# D2_2020-10-05_16-15-53.net
KiCad netlist of a schematic drawn in EasyEDA
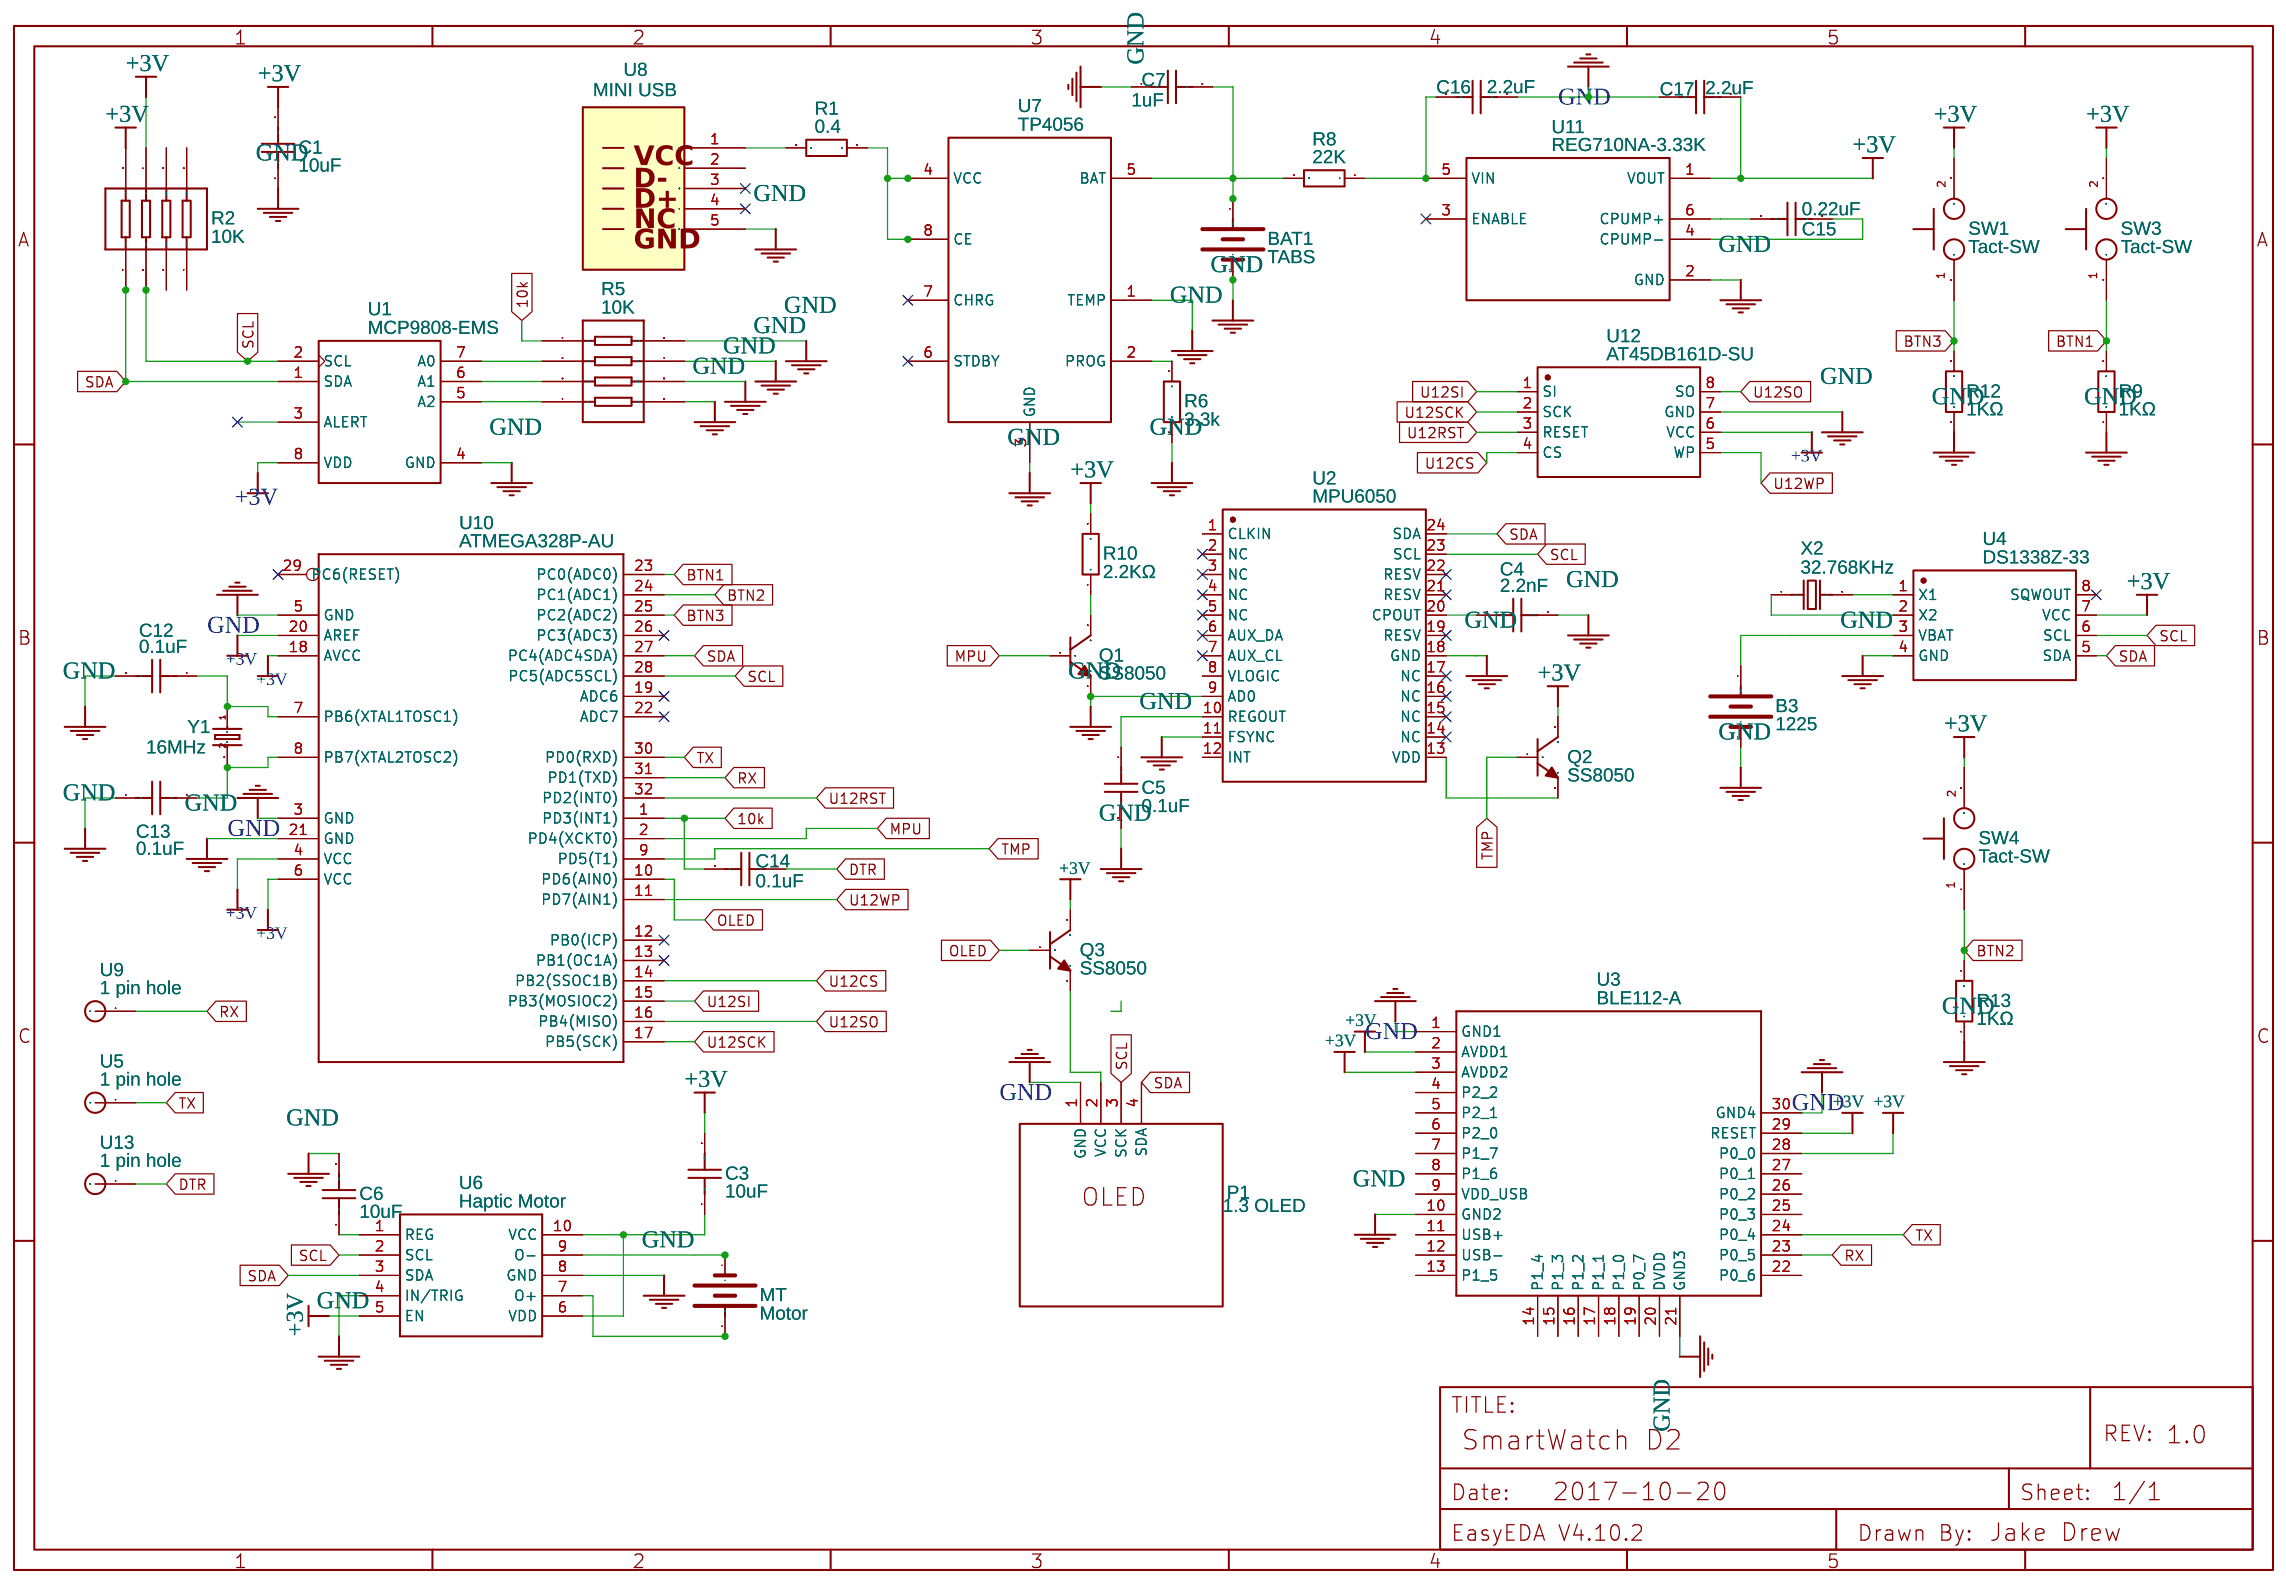
[diagram p0: schematic sheet]

(export (version "E")
  (design (tool "Eeschema 10.0.6"))
  (components
    (comp (ref "B3")
      (value "1225")
      (fields (field (name "BOM_Manufacturer Part") "?"))
      (libsource (lib "") (part "Unknown_850_335"))
    )
    (comp (ref "BAT1")
      (value "TABS")
      (fields (field (name "BOM_Manufacturer Part") "?"))
      (libsource (lib "") (part "Unknown_600_105"))
    )
    (comp (ref "C1")
      (value "10uF")
      (fields
        (field (name "BOM_Manufacturer Part") "0805B105K250NT")
        (field (name "BOM_Supplier Part") "C89190")
      )
      (libsource (lib "") (part "Unknown_130_60"))
    )
    (comp (ref "C3")
      (value "10uF")
      (fields
        (field (name "BOM_Manufacturer Part") "0805B105K250NT")
        (field (name "BOM_Supplier Part") "C89190")
      )
      (libsource (lib "") (part "Unknown_340_565"))
    )
    (comp (ref "C4")
      (value "2.2nF")
      (fields
        (field (name "BOM_Manufacturer Part") "0805B105K250NT")
        (field (name "BOM_Supplier Part") "C89190")
      )
      (libsource (lib "") (part "Unknown_740_290"))
    )
    (comp (ref "C5")
      (value "0.1uF")
      (fields
        (field (name "BOM_Manufacturer Part") "0805B105K250NT")
        (field (name "BOM_Supplier Part") "C89190")
      )
      (libsource (lib "") (part "Unknown_545_375"))
    )
    (comp (ref "C6")
      (value "10uF")
      (fields
        (field (name "BOM_Manufacturer Part") "0805B105K250NT")
        (field (name "BOM_Supplier Part") "C89190")
      )
      (libsource (lib "") (part "Unknown_160_575"))
    )
    (comp (ref "C7")
      (value "1uF")
      (fields
        (field (name "BOM_Manufacturer Part") "0805B105K250NT")
        (field (name "BOM_Supplier Part") "C89190")
      )
      (libsource (lib "") (part "Unknown_570_30"))
    )
    (comp (ref "C12")
      (value "0.1uF")
      (fields
        (field (name "BOM_Manufacturer Part") "0805B105K250NT")
        (field (name "BOM_Supplier Part") "C89190")
      )
      (libsource (lib "") (part "Unknown_70_320"))
    )
    (comp (ref "C13")
      (value "0.1uF")
      (fields
        (field (name "BOM_Manufacturer Part") "0805B105K250NT")
        (field (name "BOM_Supplier Part") "C89190")
      )
      (libsource (lib "") (part "Unknown_70_380"))
    )
    (comp (ref "C14")
      (value "0.1uF")
      (fields
        (field (name "BOM_Manufacturer Part") "0805B105K250NT")
        (field (name "BOM_Supplier Part") "C89190")
      )
      (libsource (lib "") (part "Unknown_360_415"))
    )
    (comp (ref "C15")
      (value "0.22uF")
      (fields
        (field (name "BOM_Manufacturer Part") "0805B105K250NT")
        (field (name "BOM_Supplier Part") "C89190")
      )
      (libsource (lib "") (part "Unknown_875_95"))
    )
    (comp (ref "C16")
      (value "2.2uF")
      (fields
        (field (name "BOM_Manufacturer Part") "0805B105K250NT")
        (field (name "BOM_Supplier Part") "C89190")
      )
      (libsource (lib "") (part "Unknown_720_35"))
    )
    (comp (ref "C17")
      (value "2.2uF")
      (fields
        (field (name "BOM_Manufacturer Part") "0805B105K250NT")
        (field (name "BOM_Supplier Part") "C89190")
      )
      (libsource (lib "") (part "Unknown_830_35"))
    )
    (comp (ref "MT")
      (value "Motor")
      (fields (field (name "BOM_Manufacturer Part") "?"))
      (libsource (lib "") (part "Unknown_350_625"))
    )
    (comp (ref "P1")
      (value "1.3 OLED")
      (fields (field (name "BOM_Manufacturer Part") "?"))
      (libsource (lib "") (part "Unknown_575_630"))
    )
    (comp (ref "Q1")
      (value "SS8050")
      (fields (field (name "BOM_Supplier Part") "C2150"))
      (libsource (lib "") (part "Unknown_520_310"))
    )
    (comp (ref "Q2")
      (value "SS8050")
      (fields (field (name "BOM_Supplier Part") "C2150"))
      (libsource (lib "") (part "Unknown_750_360"))
    )
    (comp (ref "Q3")
      (value "SS8050")
      (fields (field (name "BOM_Supplier Part") "C2150"))
      (libsource (lib "") (part "Unknown_510_455"))
    )
    (comp (ref "R1")
      (value "0.4")
      (fields
        (field (name "BOM_Manufacturer Part") "0805W8F147KT5E")
        (field (name "BOM_Supplier Part") "C68930")
      )
      (libsource (lib "") (part "Unknown_400_60"))
    )
    (comp (ref "R2")
      (value "10K")
      (fields
        (field (name "BOM_Manufacturer Part") "4D03WGJ0102T5E")
        (field (name "BOM_Supplier Part") "C20197")
      )
      (libsource (lib "") (part "Unknown_70_95"))
    )
    (comp (ref "R5")
      (value "10K")
      (fields
        (field (name "BOM_Manufacturer Part") "4D03WGJ0102T5E")
        (field (name "BOM_Supplier Part") "C20197")
      )
      (libsource (lib "") (part "Unknown_295_170"))
    )
    (comp (ref "R6")
      (value "3.3k")
      (fields
        (field (name "BOM_Manufacturer Part") "1210W3F680KT5E")
        (field (name "BOM_Supplier Part") "C38887")
      )
      (libsource (lib "") (part "Unknown_570_185"))
    )
    (comp (ref "R8")
      (value "22K")
      (fields
        (field (name "BOM_Manufacturer Part") "1206W4F1001T5E")
        (field (name "BOM_Supplier Part") "C4410")
      )
      (libsource (lib "") (part "Unknown_645_75"))
    )
    (comp (ref "R9")
      (value "1KΩ")
      (fields
        (field (name "BOM_Manufacturer Part") "1206W4F1001T5E")
        (field (name "BOM_Supplier Part") "C4410")
      )
      (libsource (lib "") (part "Unknown_1030_180"))
    )
    (comp (ref "R10")
      (value "2.2KΩ")
      (fields
        (field (name "BOM_Manufacturer Part") "0805W8F2201T5E")
        (field (name "BOM_Supplier Part") "C17520")
      )
      (libsource (lib "") (part "Unknown_530_260"))
    )
    (comp (ref "R12")
      (value "1KΩ")
      (fields
        (field (name "BOM_Manufacturer Part") "1206W4F1001T5E")
        (field (name "BOM_Supplier Part") "C4410")
      )
      (libsource (lib "") (part "Unknown_955_180"))
    )
    (comp (ref "R13")
      (value "1KΩ")
      (fields
        (field (name "BOM_Manufacturer Part") "1206W4F1001T5E")
        (field (name "BOM_Supplier Part") "C4410")
      )
      (libsource (lib "") (part "Unknown_960_480"))
    )
    (comp (ref "SW1")
      (value "Tact-SW")
      (fields (field (name "BOM_Manufacturer Part") "TL3330AF260QG"))
      (libsource (lib "") (part "Unknown_955_100"))
    )
    (comp (ref "SW3")
      (value "Tact-SW")
      (fields (field (name "BOM_Manufacturer Part") "TL3330AF260QG"))
      (libsource (lib "") (part "Unknown_1030_100"))
    )
    (comp (ref "SW4")
      (value "Tact-SW")
      (fields (field (name "BOM_Manufacturer Part") "TL3330AF260QG"))
      (libsource (lib "") (part "Unknown_960_400"))
    )
    (comp (ref "U1")
      (value "MCP9808-EMS")
      (fields (field (name "BOM_Manufacturer Part") "?"))
      (libsource (lib "") (part "Unknown_180_195"))
    )
    (comp (ref "U2")
      (value "MPU6050")
      (fields (field (name "BOM_Supplier Part") "C24112"))
      (libsource (lib "") (part "Unknown_645_240"))
    )
    (comp (ref "U3")
      (value "BLE112-A")
      (fields (field (name "BOM_Manufacturer Part") "?"))
      (libsource (lib "") (part "Unknown_690_505"))
    )
    (comp (ref "U4")
      (value "DS1338Z-33")
      (fields (field (name "BOM_Supplier Part") "C49105"))
      (libsource (lib "") (part "Unknown_975_270"))
    )
    (comp (ref "U5") (value "1 pin hole") (libsource (lib "") (part "Unknown_40_530")))
    (comp (ref "U6")
      (value "Haptic Motor")
      (fields (field (name "BOM_Manufacturer Part") "?"))
      (libsource (lib "") (part "Unknown_230_615"))
    )
    (comp (ref "U7")
      (value "TP4056")
      (fields (field (name "BOM_Supplier Part") "C16581"))
      (libsource (lib "") (part "Unknown_500_135"))
    )
    (comp (ref "U8")
      (value "MINI USB")
      (fields (field (name "BOM_Manufacturer Part") "?"))
      (libsource (lib "") (part "Unknown_330_80"))
    )
    (comp (ref "U9") (value "1 pin hole") (libsource (lib "") (part "Unknown_40_485")))
    (comp (ref "U10") (value "ATMEGA328P-AU") (libsource (lib "") (part "Unknown_225_385")))
    (comp (ref "U11")
      (value "REG710NA-3.33K")
      (fields (field (name "BOM_Manufacturer Part") "?"))
      (libsource (lib "") (part "Unknown_765_105"))
    )
    (comp (ref "U12")
      (value "AT45DB161D-SU")
      (fields (field (name "BOM_Manufacturer Part") "?"))
      (libsource (lib "") (part "Unknown_790_170"))
    )
    (comp (ref "U13") (value "1 pin hole") (libsource (lib "") (part "Unknown_40_570")))
    (comp (ref "X2")
      (value "32.768KHz")
      (fields
        (field (name "BOM_Manufacturer Part") "DT-38 32.768KHz")
        (field (name "BOM_Supplier Part") "C93228")
      )
      (libsource (lib "") (part "Unknown_885_280"))
    )
    (comp (ref "Y1")
      (value "16MHz")
      (fields (field (name "BOM_Manufacturer Part") "X053201602002"))
      (libsource (lib "") (part "Unknown_105_350"))
    )
  )
  (nets
    (net (code "1") (name "+3V") (class "Default")
      (node (ref "C1") (pin "2") (pinfunction "2_2") (pintype "unspecified"))
      (node (ref "C17") (pin "2") (pinfunction "2_2") (pintype "unspecified"))
      (node (ref "C3") (pin "2") (pinfunction "2_2") (pintype "unspecified"))
      (node (ref "Q2") (pin "3") (pinfunction "C_3") (pintype "unspecified"))
      (node (ref "Q3") (pin "3") (pinfunction "C_3") (pintype "unspecified"))
      (node (ref "R10") (pin "2") (pinfunction "2_2") (pintype "input"))
      (node (ref "R2") (pin "7") (pinfunction "7_7") (pintype "input"))
      (node (ref "R2") (pin "8") (pinfunction "8_8") (pintype "input"))
      (node (ref "SW1") (pin "2") (pinfunction "2_2") (pintype "unspecified"))
      (node (ref "SW3") (pin "2") (pinfunction "2_2") (pintype "unspecified"))
      (node (ref "SW4") (pin "2") (pinfunction "2_2") (pintype "unspecified"))
      (node (ref "U1") (pin "8") (pinfunction "VDD_8") (pintype "passive"))
      (node (ref "U10") (pin "18") (pinfunction "AVCC_18") (pintype "unspecified"))
      (node (ref "U10") (pin "20") (pinfunction "AREF_20") (pintype "unspecified"))
      (node (ref "U10") (pin "4") (pinfunction "VCC_4") (pintype "unspecified"))
      (node (ref "U10") (pin "6") (pinfunction "VCC_6") (pintype "unspecified"))
      (node (ref "U11") (pin "1") (pinfunction "VOUT_1") (pintype "passive"))
      (node (ref "U12") (pin "6") (pinfunction "VCC_6") (pintype "unspecified"))
      (node (ref "U3") (pin "2") (pinfunction "AVDD1_2") (pintype "unspecified"))
      (node (ref "U3") (pin "28") (pinfunction "P0_0_28") (pintype "unspecified"))
      (node (ref "U3") (pin "29") (pinfunction "RESET_29") (pintype "unspecified"))
      (node (ref "U3") (pin "3") (pinfunction "AVDD2_3") (pintype "unspecified"))
      (node (ref "U4") (pin "7") (pinfunction "VCC_7") (pintype "unspecified"))
      (node (ref "U6") (pin "5") (pinfunction "EN_5") (pintype "unspecified"))
    )
    (net (code "2") (name "10k") (class "Default")
      (node (ref "C14") (pin "2") (pinfunction "2_2") (pintype "unspecified"))
      (node (ref "R5") (pin "1") (pinfunction "1_1") (pintype "input"))
      (node (ref "U10") (pin "1") (pinfunction "PD3(INT1)_1") (pintype "unspecified"))
    )
    (net (code "3") (name "BTN1") (class "Default")
      (node (ref "R9") (pin "2") (pinfunction "2_2") (pintype "input"))
      (node (ref "SW3") (pin "1") (pinfunction "1_1") (pintype "unspecified"))
      (node (ref "U10") (pin "23") (pinfunction "PC0(ADC0)_23") (pintype "unspecified"))
    )
    (net (code "4") (name "BTN2") (class "Default")
      (node (ref "R13") (pin "2") (pinfunction "2_2") (pintype "input"))
      (node (ref "SW4") (pin "1") (pinfunction "1_1") (pintype "unspecified"))
      (node (ref "U10") (pin "24") (pinfunction "PC1(ADC1)_24") (pintype "unspecified"))
    )
    (net (code "5") (name "BTN3") (class "Default")
      (node (ref "R12") (pin "2") (pinfunction "2_2") (pintype "input"))
      (node (ref "SW1") (pin "1") (pinfunction "1_1") (pintype "unspecified"))
      (node (ref "U10") (pin "25") (pinfunction "PC2(ADC2)_25") (pintype "unspecified"))
    )
    (net (code "6") (name "DTR") (class "Default")
      (node (ref "C14") (pin "1") (pinfunction "1_1") (pintype "unspecified"))
      (node (ref "U13") (pin "1") (pinfunction "1_1") (pintype "unspecified"))
    )
    (net (code "7") (name "GND") (class "Default")
      (node (ref "B3") (pin "-") (pinfunction "-_-") (pintype "passive"))
      (node (ref "BAT1") (pin "-") (pinfunction "-_-") (pintype "passive"))
      (node (ref "C1") (pin "1") (pinfunction "1_1") (pintype "unspecified"))
      (node (ref "C12") (pin "2") (pinfunction "2_2") (pintype "unspecified"))
      (node (ref "C13") (pin "1") (pinfunction "1_1") (pintype "unspecified"))
      (node (ref "C16") (pin "1") (pinfunction "1_1") (pintype "unspecified"))
      (node (ref "C17") (pin "1") (pinfunction "1_1") (pintype "unspecified"))
      (node (ref "C4") (pin "1") (pinfunction "1_1") (pintype "unspecified"))
      (node (ref "C5") (pin "2") (pinfunction "2_2") (pintype "unspecified"))
      (node (ref "C6") (pin "2") (pinfunction "2_2") (pintype "unspecified"))
      (node (ref "C7") (pin "1") (pinfunction "1_1") (pintype "unspecified"))
      (node (ref "P1") (pin "1") (pinfunction "GND_1") (pintype "unspecified"))
      (node (ref "Q1") (pin "2") (pinfunction "E_2") (pintype "unspecified"))
      (node (ref "R12") (pin "1") (pinfunction "1_1") (pintype "input"))
      (node (ref "R13") (pin "1") (pinfunction "1_1") (pintype "input"))
      (node (ref "R5") (pin "5") (pinfunction "5_5") (pintype "input"))
      (node (ref "R5") (pin "6") (pinfunction "6_6") (pintype "input"))
      (node (ref "R5") (pin "7") (pinfunction "7_7") (pintype "input"))
      (node (ref "R5") (pin "8") (pinfunction "8_8") (pintype "input"))
      (node (ref "R6") (pin "1") (pinfunction "1_1") (pintype "input"))
      (node (ref "R9") (pin "1") (pinfunction "1_1") (pintype "input"))
      (node (ref "U1") (pin "4") (pinfunction "GND_4") (pintype "passive"))
      (node (ref "U10") (pin "21") (pinfunction "GND_21") (pintype "unspecified"))
      (node (ref "U10") (pin "3") (pinfunction "GND_3") (pintype "unspecified"))
      (node (ref "U10") (pin "5") (pinfunction "GND_5") (pintype "unspecified"))
      (node (ref "U11") (pin "2") (pinfunction "GND_2") (pintype "passive"))
      (node (ref "U12") (pin "7") (pinfunction "GND_7") (pintype "unspecified"))
      (node (ref "U2") (pin "11") (pinfunction "FSYNC_11") (pintype "unspecified"))
      (node (ref "U2") (pin "18") (pinfunction "GND_18") (pintype "unspecified"))
      (node (ref "U2") (pin "9") (pinfunction "AD0_9") (pintype "unspecified"))
      (node (ref "U3") (pin "1") (pinfunction "GND1_1") (pintype "unspecified"))
      (node (ref "U3") (pin "10") (pinfunction "GND2_10") (pintype "unspecified"))
      (node (ref "U3") (pin "21") (pinfunction "GND3_21") (pintype "unspecified"))
      (node (ref "U3") (pin "30") (pinfunction "GND4_30") (pintype "unspecified"))
      (node (ref "U4") (pin "4") (pinfunction "GND_4") (pintype "unspecified"))
      (node (ref "U6") (pin "4") (pinfunction "IN/TRIG_4") (pintype "unspecified"))
      (node (ref "U6") (pin "8") (pinfunction "GND_8") (pintype "unspecified"))
      (node (ref "U7") (pin "1") (pinfunction "TEMP_1") (pintype "unspecified"))
      (node (ref "U7") (pin "3") (pinfunction "GND_3") (pintype "unspecified"))
      (node (ref "U8") (pin "5") (pinfunction "5_5") (pintype "unspecified"))
    )
    (net (code "8") (name "MPU") (class "Default")
      (node (ref "Q1") (pin "1") (pinfunction "B_1") (pintype "unspecified"))
      (node (ref "U10") (pin "2") (pinfunction "PD4(XCKT0)_2") (pintype "unspecified"))
    )
    (net (code "9") (name "Net-(P1-VCC)") (class "Default")
      (node (ref "P1") (pin "2") (pinfunction "VCC_2") (pintype "unspecified"))
      (node (ref "Q3") (pin "2") (pinfunction "E_2") (pintype "unspecified"))
    )
    (net (code "10") (name "Net-(Q1-C)") (class "Default")
      (node (ref "Q1") (pin "3") (pinfunction "C_3") (pintype "unspecified"))
      (node (ref "R10") (pin "1") (pinfunction "1_1") (pintype "input"))
    )
    (net (code "11") (name "Net-(Q2-E)") (class "Default")
      (node (ref "Q2") (pin "2") (pinfunction "E_2") (pintype "unspecified"))
      (node (ref "U2") (pin "13") (pinfunction "VDD_13") (pintype "unspecified"))
    )
    (net (code "12") (name "Net-(R1-Pad2)") (class "Default")
      (node (ref "R1") (pin "2") (pinfunction "2_2") (pintype "input"))
      (node (ref "U8") (pin "1") (pinfunction "1_1") (pintype "unspecified"))
    )
    (net (code "13") (name "Net-(U1-A0)") (class "Default")
      (node (ref "R5") (pin "2") (pinfunction "2_2") (pintype "input"))
      (node (ref "U1") (pin "7") (pinfunction "A0_7") (pintype "unspecified"))
    )
    (net (code "14") (name "Net-(U1-A1)") (class "Default")
      (node (ref "R5") (pin "3") (pinfunction "3_3") (pintype "input"))
      (node (ref "U1") (pin "6") (pinfunction "A1_6") (pintype "unspecified"))
    )
    (net (code "15") (name "Net-(U1-A2)") (class "Default")
      (node (ref "R5") (pin "4") (pinfunction "4_4") (pintype "input"))
      (node (ref "U1") (pin "5") (pinfunction "A2_5") (pintype "unspecified"))
    )
    (net (code "16") (name "Net-(U2-CPOUT)") (class "Default")
      (node (ref "C4") (pin "2") (pinfunction "2_2") (pintype "unspecified"))
      (node (ref "U2") (pin "20") (pinfunction "CPOUT_20") (pintype "unspecified"))
    )
    (net (code "17") (name "Net-(U2-REGOUT)") (class "Default")
      (node (ref "C5") (pin "1") (pinfunction "1_1") (pintype "unspecified"))
      (node (ref "U2") (pin "10") (pinfunction "REGOUT_10") (pintype "unspecified"))
    )
    (net (code "18") (name "Net-(U4-VBAT)") (class "Default")
      (node (ref "B3") (pin "+") (pinfunction "+_+") (pintype "passive"))
      (node (ref "U4") (pin "3") (pinfunction "VBAT_3") (pintype "unspecified"))
    )
    (net (code "19") (name "Net-(U4-X1)") (class "Default")
      (node (ref "U4") (pin "1") (pinfunction "X1_1") (pintype "unspecified"))
      (node (ref "X2") (pin "2") (pinfunction "2_2") (pintype "unspecified"))
    )
    (net (code "20") (name "Net-(U4-X2)") (class "Default")
      (node (ref "U4") (pin "2") (pinfunction "X2_2") (pintype "unspecified"))
      (node (ref "X2") (pin "1") (pinfunction "1_1") (pintype "unspecified"))
    )
    (net (code "21") (name "Net-(U6-O+)") (class "Default")
      (node (ref "MT") (pin "+") (pinfunction "+_+") (pintype "passive"))
      (node (ref "U6") (pin "7") (pinfunction "O+_7") (pintype "unspecified"))
    )
    (net (code "22") (name "Net-(U6-O-)") (class "Default")
      (node (ref "MT") (pin "-") (pinfunction "-_-") (pintype "passive"))
      (node (ref "U6") (pin "9") (pinfunction "O-_9") (pintype "unspecified"))
    )
    (net (code "23") (name "Net-(U6-REG)") (class "Default")
      (node (ref "C6") (pin "1") (pinfunction "1_1") (pintype "unspecified"))
      (node (ref "U6") (pin "1") (pinfunction "REG_1") (pintype "unspecified"))
    )
    (net (code "24") (name "Net-(U6-VCC)") (class "Default")
      (node (ref "C3") (pin "1") (pinfunction "1_1") (pintype "unspecified"))
      (node (ref "U6") (pin "10") (pinfunction "VCC_10") (pintype "unspecified"))
      (node (ref "U6") (pin "6") (pinfunction "VDD_6") (pintype "unspecified"))
    )
    (net (code "25") (name "Net-(U7-BAT)") (class "Default")
      (node (ref "BAT1") (pin "+") (pinfunction "+_+") (pintype "passive"))
      (node (ref "C7") (pin "2") (pinfunction "2_2") (pintype "unspecified"))
      (node (ref "R8") (pin "2") (pinfunction "2_2") (pintype "input"))
      (node (ref "U7") (pin "5") (pinfunction "BAT_5") (pintype "unspecified"))
    )
    (net (code "26") (name "Net-(U7-CE)") (class "Default")
      (node (ref "R1") (pin "1") (pinfunction "1_1") (pintype "input"))
      (node (ref "U7") (pin "4") (pinfunction "VCC_4") (pintype "unspecified"))
      (node (ref "U7") (pin "8") (pinfunction "CE_8") (pintype "unspecified"))
    )
    (net (code "27") (name "Net-(U7-PROG)") (class "Default")
      (node (ref "R6") (pin "2") (pinfunction "2_2") (pintype "input"))
      (node (ref "U7") (pin "2") (pinfunction "PROG_2") (pintype "unspecified"))
    )
    (net (code "28") (name "Net-(U10-PB6(XTAL1TOSC1))") (class "Default")
      (node (ref "C12") (pin "1") (pinfunction "1_1") (pintype "unspecified"))
      (node (ref "U10") (pin "7") (pinfunction "PB6(XTAL1TOSC1)_7") (pintype "unspecified"))
      (node (ref "Y1") (pin "1") (pinfunction "1_1") (pintype "unspecified"))
    )
    (net (code "29") (name "Net-(U10-PB7(XTAL2TOSC2))") (class "Default")
      (node (ref "C13") (pin "2") (pinfunction "2_2") (pintype "unspecified"))
      (node (ref "U10") (pin "8") (pinfunction "PB7(XTAL2TOSC2)_8") (pintype "unspecified"))
      (node (ref "Y1") (pin "2") (pinfunction "2_2") (pintype "unspecified"))
    )
    (net (code "30") (name "Net-(U11-CPUMP+)") (class "Default")
      (node (ref "C15") (pin "1") (pinfunction "1_1") (pintype "unspecified"))
      (node (ref "U11") (pin "6") (pinfunction "CPUMP+_6") (pintype "unspecified"))
    )
    (net (code "31") (name "Net-(U11-CPUMP-)") (class "Default")
      (node (ref "C15") (pin "2") (pinfunction "2_2") (pintype "unspecified"))
      (node (ref "U11") (pin "4") (pinfunction "CPUMP-_4") (pintype "unspecified"))
    )
    (net (code "32") (name "Net-(U11-VIN)") (class "Default")
      (node (ref "C16") (pin "2") (pinfunction "2_2") (pintype "unspecified"))
      (node (ref "R8") (pin "1") (pinfunction "1_1") (pintype "input"))
      (node (ref "U11") (pin "5") (pinfunction "VIN_5") (pintype "passive"))
    )
    (net (code "33") (name "OLED") (class "Default")
      (node (ref "Q3") (pin "1") (pinfunction "B_1") (pintype "unspecified"))
      (node (ref "U10") (pin "10") (pinfunction "PD6(AIN0)_10") (pintype "unspecified"))
    )
    (net (code "34") (name "RX") (class "Default")
      (node (ref "U10") (pin "31") (pinfunction "PD1(TXD)_31") (pintype "unspecified"))
      (node (ref "U3") (pin "23") (pinfunction "P0_5_23") (pintype "unspecified"))
      (node (ref "U9") (pin "1") (pinfunction "1_1") (pintype "unspecified"))
    )
    (net (code "35") (name "SCL") (class "Default")
      (node (ref "P1") (pin "3") (pinfunction "SCK_3") (pintype "unspecified"))
      (node (ref "R2") (pin "2") (pinfunction "2_2") (pintype "input"))
      (node (ref "U1") (pin "2") (pinfunction "SCL_2") (pintype "unspecified"))
      (node (ref "U10") (pin "28") (pinfunction "PC5(ADC5SCL)_28") (pintype "unspecified"))
      (node (ref "U2") (pin "23") (pinfunction "SCL_23") (pintype "unspecified"))
      (node (ref "U4") (pin "6") (pinfunction "SCL_6") (pintype "unspecified"))
      (node (ref "U6") (pin "2") (pinfunction "SCL_2") (pintype "unspecified"))
    )
    (net (code "36") (name "SDA") (class "Default")
      (node (ref "P1") (pin "4") (pinfunction "SDA_4") (pintype "unspecified"))
      (node (ref "R2") (pin "1") (pinfunction "1_1") (pintype "input"))
      (node (ref "U1") (pin "1") (pinfunction "SDA_1") (pintype "bidirectional"))
      (node (ref "U10") (pin "27") (pinfunction "PC4(ADC4SDA)_27") (pintype "unspecified"))
      (node (ref "U2") (pin "24") (pinfunction "SDA_24") (pintype "unspecified"))
      (node (ref "U4") (pin "5") (pinfunction "SDA_5") (pintype "unspecified"))
      (node (ref "U6") (pin "3") (pinfunction "SDA_3") (pintype "unspecified"))
    )
    (net (code "37") (name "TMP") (class "Default")
      (node (ref "Q2") (pin "1") (pinfunction "B_1") (pintype "unspecified"))
      (node (ref "U10") (pin "9") (pinfunction "PD5(T1)_9") (pintype "unspecified"))
    )
    (net (code "38") (name "TX") (class "Default")
      (node (ref "U10") (pin "30") (pinfunction "PD0(RXD)_30") (pintype "unspecified"))
      (node (ref "U3") (pin "24") (pinfunction "P0_4_24") (pintype "unspecified"))
      (node (ref "U5") (pin "1") (pinfunction "1_1") (pintype "unspecified"))
    )
    (net (code "39") (name "U12CS") (class "Default")
      (node (ref "U10") (pin "14") (pinfunction "PB2(SSOC1B)_14") (pintype "unspecified"))
      (node (ref "U12") (pin "4") (pinfunction "CS_4") (pintype "unspecified"))
    )
    (net (code "40") (name "U12RST") (class "Default")
      (node (ref "U10") (pin "32") (pinfunction "PD2(INT0)_32") (pintype "unspecified"))
      (node (ref "U12") (pin "3") (pinfunction "RESET_3") (pintype "unspecified"))
    )
    (net (code "41") (name "U12SCK") (class "Default")
      (node (ref "U10") (pin "17") (pinfunction "PB5(SCK)_17") (pintype "unspecified"))
      (node (ref "U12") (pin "2") (pinfunction "SCK_2") (pintype "unspecified"))
    )
    (net (code "42") (name "U12SI") (class "Default")
      (node (ref "U10") (pin "15") (pinfunction "PB3(MOSIOC2)_15") (pintype "unspecified"))
      (node (ref "U12") (pin "1") (pinfunction "SI_1") (pintype "unspecified"))
    )
    (net (code "43") (name "U12SO") (class "Default")
      (node (ref "U10") (pin "16") (pinfunction "PB4(MISO)_16") (pintype "unspecified"))
      (node (ref "U12") (pin "8") (pinfunction "SO_8") (pintype "unspecified"))
    )
    (net (code "44") (name "U12WP") (class "Default")
      (node (ref "U10") (pin "11") (pinfunction "PD7(AIN1)_11") (pintype "unspecified"))
      (node (ref "U12") (pin "5") (pinfunction "WP_5") (pintype "unspecified"))
    )
    (net (code "45") (name "unconnected-(R2-Pad3)") (class "Default")
      (node (ref "R2") (pin "3") (pinfunction "3_3") (pintype "input"))
    )
    (net (code "46") (name "unconnected-(R2-Pad4)") (class "Default")
      (node (ref "R2") (pin "4") (pinfunction "4_4") (pintype "input"))
    )
    (net (code "47") (name "unconnected-(R2-Pad5)") (class "Default")
      (node (ref "R2") (pin "5") (pinfunction "5_5") (pintype "input"))
    )
    (net (code "48") (name "unconnected-(R2-Pad6)") (class "Default")
      (node (ref "R2") (pin "6") (pinfunction "6_6") (pintype "input"))
    )
    (net (code "49") (name "unconnected-(U1-ALERT-Pad3)") (class "Default")
      (node (ref "U1") (pin "3") (pinfunction "ALERT_3") (pintype "unspecified+no_connect"))
    )
    (net (code "50") (name "unconnected-(U2-AUX_CL-Pad7)") (class "Default")
      (node (ref "U2") (pin "7") (pinfunction "AUX_CL_7") (pintype "unspecified+no_connect"))
    )
    (net (code "51") (name "unconnected-(U2-AUX_DA-Pad6)") (class "Default")
      (node (ref "U2") (pin "6") (pinfunction "AUX_DA_6") (pintype "unspecified+no_connect"))
    )
    (net (code "52") (name "unconnected-(U2-CLKIN-Pad1)") (class "Default")
      (node (ref "U2") (pin "1") (pinfunction "CLKIN_1") (pintype "unspecified"))
    )
    (net (code "53") (name "unconnected-(U2-INT-Pad12)") (class "Default")
      (node (ref "U2") (pin "12") (pinfunction "INT_12") (pintype "unspecified"))
    )
    (net (code "54") (name "unconnected-(U2-NC-Pad2)") (class "Default")
      (node (ref "U2") (pin "2") (pinfunction "NC_2") (pintype "unspecified+no_connect"))
    )
    (net (code "55") (name "unconnected-(U2-NC-Pad3)") (class "Default")
      (node (ref "U2") (pin "3") (pinfunction "NC_3") (pintype "unspecified+no_connect"))
    )
    (net (code "56") (name "unconnected-(U2-NC-Pad4)") (class "Default")
      (node (ref "U2") (pin "4") (pinfunction "NC_4") (pintype "unspecified+no_connect"))
    )
    (net (code "57") (name "unconnected-(U2-NC-Pad5)") (class "Default")
      (node (ref "U2") (pin "5") (pinfunction "NC_5") (pintype "unspecified+no_connect"))
    )
    (net (code "58") (name "unconnected-(U2-NC-Pad14)") (class "Default")
      (node (ref "U2") (pin "14") (pinfunction "NC_14") (pintype "unspecified+no_connect"))
    )
    (net (code "59") (name "unconnected-(U2-NC-Pad15)") (class "Default")
      (node (ref "U2") (pin "15") (pinfunction "NC_15") (pintype "unspecified+no_connect"))
    )
    (net (code "60") (name "unconnected-(U2-NC-Pad16)") (class "Default")
      (node (ref "U2") (pin "16") (pinfunction "NC_16") (pintype "unspecified+no_connect"))
    )
    (net (code "61") (name "unconnected-(U2-NC-Pad17)") (class "Default")
      (node (ref "U2") (pin "17") (pinfunction "NC_17") (pintype "unspecified+no_connect"))
    )
    (net (code "62") (name "unconnected-(U2-RESV-Pad19)") (class "Default")
      (node (ref "U2") (pin "19") (pinfunction "RESV_19") (pintype "unspecified+no_connect"))
    )
    (net (code "63") (name "unconnected-(U2-RESV-Pad21)") (class "Default")
      (node (ref "U2") (pin "21") (pinfunction "RESV_21") (pintype "unspecified+no_connect"))
    )
    (net (code "64") (name "unconnected-(U2-RESV-Pad22)") (class "Default")
      (node (ref "U2") (pin "22") (pinfunction "RESV_22") (pintype "unspecified+no_connect"))
    )
    (net (code "65") (name "unconnected-(U2-VLOGIC-Pad8)") (class "Default")
      (node (ref "U2") (pin "8") (pinfunction "VLOGIC_8") (pintype "unspecified"))
    )
    (net (code "66") (name "unconnected-(U3-DVDD-Pad20)") (class "Default")
      (node (ref "U3") (pin "20") (pinfunction "DVDD_20") (pintype "unspecified"))
    )
    (net (code "67") (name "unconnected-(U3-P0_1-Pad27)") (class "Default")
      (node (ref "U3") (pin "27") (pinfunction "P0_1_27") (pintype "unspecified"))
    )
    (net (code "68") (name "unconnected-(U3-P0_2-Pad26)") (class "Default")
      (node (ref "U3") (pin "26") (pinfunction "P0_2_26") (pintype "unspecified"))
    )
    (net (code "69") (name "unconnected-(U3-P0_3-Pad25)") (class "Default")
      (node (ref "U3") (pin "25") (pinfunction "P0_3_25") (pintype "unspecified"))
    )
    (net (code "70") (name "unconnected-(U3-P0_6-Pad22)") (class "Default")
      (node (ref "U3") (pin "22") (pinfunction "P0_6_22") (pintype "unspecified"))
    )
    (net (code "71") (name "unconnected-(U3-P0_7-Pad19)") (class "Default")
      (node (ref "U3") (pin "19") (pinfunction "P0_7_19") (pintype "unspecified"))
    )
    (net (code "72") (name "unconnected-(U3-P1_0-Pad18)") (class "Default")
      (node (ref "U3") (pin "18") (pinfunction "P1_0_18") (pintype "unspecified"))
    )
    (net (code "73") (name "unconnected-(U3-P1_1-Pad17)") (class "Default")
      (node (ref "U3") (pin "17") (pinfunction "P1_1_17") (pintype "unspecified"))
    )
    (net (code "74") (name "unconnected-(U3-P1_2-Pad16)") (class "Default")
      (node (ref "U3") (pin "16") (pinfunction "P1_2_16") (pintype "unspecified"))
    )
    (net (code "75") (name "unconnected-(U3-P1_3-Pad15)") (class "Default")
      (node (ref "U3") (pin "15") (pinfunction "P1_3_15") (pintype "unspecified"))
    )
    (net (code "76") (name "unconnected-(U3-P1_4-Pad14)") (class "Default")
      (node (ref "U3") (pin "14") (pinfunction "P1_4_14") (pintype "unspecified"))
    )
    (net (code "77") (name "unconnected-(U3-P1_5-Pad13)") (class "Default")
      (node (ref "U3") (pin "13") (pinfunction "P1_5_13") (pintype "unspecified"))
    )
    (net (code "78") (name "unconnected-(U3-P1_6-Pad8)") (class "Default")
      (node (ref "U3") (pin "8") (pinfunction "P1_6_8") (pintype "unspecified"))
    )
    (net (code "79") (name "unconnected-(U3-P1_7-Pad7)") (class "Default")
      (node (ref "U3") (pin "7") (pinfunction "P1_7_7") (pintype "unspecified"))
    )
    (net (code "80") (name "unconnected-(U3-P2_0-Pad6)") (class "Default")
      (node (ref "U3") (pin "6") (pinfunction "P2_0_6") (pintype "unspecified"))
    )
    (net (code "81") (name "unconnected-(U3-P2_1-Pad5)") (class "Default")
      (node (ref "U3") (pin "5") (pinfunction "P2_1_5") (pintype "unspecified"))
    )
    (net (code "82") (name "unconnected-(U3-P2_2-Pad4)") (class "Default")
      (node (ref "U3") (pin "4") (pinfunction "P2_2_4") (pintype "unspecified"))
    )
    (net (code "83") (name "unconnected-(U3-USB+-Pad11)") (class "Default")
      (node (ref "U3") (pin "11") (pinfunction "USB+_11") (pintype "unspecified"))
    )
    (net (code "84") (name "unconnected-(U3-USB--Pad12)") (class "Default")
      (node (ref "U3") (pin "12") (pinfunction "USB-_12") (pintype "unspecified"))
    )
    (net (code "85") (name "unconnected-(U3-VDD_USB-Pad9)") (class "Default")
      (node (ref "U3") (pin "9") (pinfunction "VDD_USB_9") (pintype "unspecified"))
    )
    (net (code "86") (name "unconnected-(U4-SQWOUT-Pad8)") (class "Default")
      (node (ref "U4") (pin "8") (pinfunction "SQWOUT_8") (pintype "unspecified+no_connect"))
    )
    (net (code "87") (name "unconnected-(U7-CHRG-Pad7)") (class "Default")
      (node (ref "U7") (pin "7") (pinfunction "CHRG_7") (pintype "unspecified+no_connect"))
    )
    (net (code "88") (name "unconnected-(U7-STDBY-Pad6)") (class "Default")
      (node (ref "U7") (pin "6") (pinfunction "STDBY_6") (pintype "unspecified+no_connect"))
    )
    (net (code "89") (name "unconnected-(U8-Pad2)") (class "Default")
      (node (ref "U8") (pin "2") (pinfunction "2_2") (pintype "unspecified"))
    )
    (net (code "90") (name "unconnected-(U8-Pad3)") (class "Default")
      (node (ref "U8") (pin "3") (pinfunction "3_3") (pintype "unspecified+no_connect"))
    )
    (net (code "91") (name "unconnected-(U8-Pad4)") (class "Default")
      (node (ref "U8") (pin "4") (pinfunction "4_4") (pintype "unspecified+no_connect"))
    )
    (net (code "92") (name "unconnected-(U10-ADC6-Pad19)") (class "Default")
      (node (ref "U10") (pin "19") (pinfunction "ADC6_19") (pintype "unspecified+no_connect"))
    )
    (net (code "93") (name "unconnected-(U10-ADC7-Pad22)") (class "Default")
      (node (ref "U10") (pin "22") (pinfunction "ADC7_22") (pintype "unspecified+no_connect"))
    )
    (net (code "94") (name "unconnected-(U10-PB0(ICP)-Pad12)") (class "Default")
      (node (ref "U10") (pin "12") (pinfunction "PB0(ICP)_12") (pintype "unspecified+no_connect"))
    )
    (net (code "95") (name "unconnected-(U10-PB1(OC1A)-Pad13)") (class "Default")
      (node (ref "U10") (pin "13") (pinfunction "PB1(OC1A)_13") (pintype "unspecified+no_connect"))
    )
    (net (code "96") (name "unconnected-(U10-PC3(ADC3)-Pad26)") (class "Default")
      (node (ref "U10") (pin "26") (pinfunction "PC3(ADC3)_26") (pintype "unspecified+no_connect"))
    )
    (net (code "97") (name "unconnected-(U10-PC6(RESET)-Pad29)") (class "Default")
      (node (ref "U10") (pin "29") (pinfunction "PC6(RESET)_29") (pintype "unspecified+no_connect"))
    )
    (net (code "98") (name "unconnected-(U11-ENABLE-Pad3)") (class "Default")
      (node (ref "U11") (pin "3") (pinfunction "ENABLE_3") (pintype "unspecified+no_connect"))
    )
  )
)
